# Sheet1.net
KiCad netlist of a schematic drawn in Altium Designer
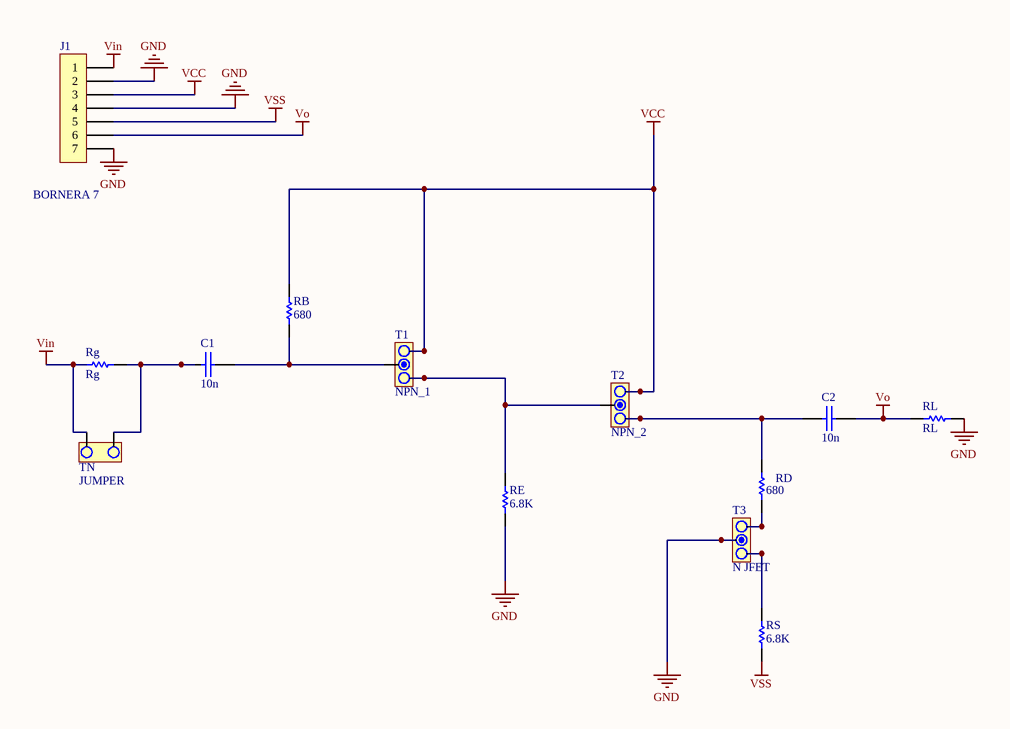
[diagram p0: Sheet1.SchDoc]

(export (version "E")
  (design (tool "Eeschema 10.0.6"))
  (components
    (comp (ref "C1") (value "10n") (footprint "0805") (libsource (lib "LIBEBAL") (part "CAP")))
    (comp (ref "C2") (value "10n") (footprint "0805") (libsource (lib "LIBEBAL") (part "CAP")))
    (comp (ref "J1")
      (value "BORNERA 7")
      (footprint "BORNERA7")
      (libsource (lib "LIBEBAL") (part "BORNERA 7"))
    )
    (comp (ref "RB") (value "680") (footprint "0805") (libsource (lib "LIBEBAL") (part "RES")))
    (comp (ref "RD") (value "680") (footprint "0805") (libsource (lib "LIBEBAL") (part "RES")))
    (comp (ref "RE") (value "6.8K") (footprint "0805") (libsource (lib "LIBEBAL") (part "RES")))
    (comp (ref "Rg") (value "Rg") (footprint "0805") (libsource (lib "LIBEBAL") (part "RES")))
    (comp (ref "RL") (value "RL") (footprint "0805") (libsource (lib "LIBEBAL") (part "RES")))
    (comp (ref "RS") (value "6.8K") (footprint "0805") (libsource (lib "LIBEBAL") (part "RES")))
    (comp (ref "T1") (value "NPN_1") (footprint "JUMPER3") (libsource (lib "LIBEBAL") (part "JUMPER3")))
    (comp (ref "T2") (value "NPN_2") (footprint "JUMPER3") (libsource (lib "LIBEBAL") (part "JUMPER3")))
    (comp (ref "T3") (value "N JFET") (footprint "JUMPER3") (libsource (lib "LIBEBAL") (part "JUMPER3")))
    (comp (ref "TN") (value "JUMPER") (footprint "JUMPER2") (libsource (lib "LIBEBAL") (part "JUMPER")))
  )
  (nets
    (net (code "1") (name "GND") (class "Default")
      (node (ref "J1") (pin "2") (pinfunction "2_2") (pintype "passive"))
      (node (ref "J1") (pin "4") (pinfunction "4_4") (pintype "passive"))
      (node (ref "J1") (pin "7") (pinfunction "7_7") (pintype "passive"))
      (node (ref "RE") (pin "1") (pinfunction "1_1") (pintype "passive"))
      (node (ref "RL") (pin "2") (pinfunction "2_2") (pintype "passive"))
      (node (ref "T3") (pin "2") (pinfunction "2_2") (pintype "passive"))
    )
    (net (code "2") (name "Net-(C1-Pad1)") (class "Default")
      (node (ref "C1") (pin "1") (pinfunction "1_1") (pintype "passive"))
      (node (ref "Rg") (pin "2") (pinfunction "2_2") (pintype "passive"))
      (node (ref "TN") (pin "2") (pinfunction "2_2") (pintype "passive"))
    )
    (net (code "3") (name "Net-(C1-Pad2)") (class "Default")
      (node (ref "C1") (pin "2") (pinfunction "2_2") (pintype "passive"))
      (node (ref "RB") (pin "1") (pinfunction "1_1") (pintype "passive"))
      (node (ref "T1") (pin "2") (pinfunction "2_2") (pintype "passive"))
    )
    (net (code "4") (name "Net-(C2-Pad1)") (class "Default")
      (node (ref "C2") (pin "1") (pinfunction "1_1") (pintype "passive"))
      (node (ref "RD") (pin "2") (pinfunction "2_2") (pintype "passive"))
      (node (ref "T2") (pin "3") (pinfunction "3_3") (pintype "passive"))
    )
    (net (code "5") (name "Net-(RD-Pad1)") (class "Default")
      (node (ref "RD") (pin "1") (pinfunction "1_1") (pintype "passive"))
      (node (ref "T3") (pin "1") (pinfunction "1_1") (pintype "passive"))
    )
    (net (code "6") (name "Net-(RE-Pad2)") (class "Default")
      (node (ref "RE") (pin "2") (pinfunction "2_2") (pintype "passive"))
      (node (ref "T1") (pin "3") (pinfunction "3_3") (pintype "passive"))
      (node (ref "T2") (pin "2") (pinfunction "2_2") (pintype "passive"))
    )
    (net (code "7") (name "Net-(RS-Pad2)") (class "Default")
      (node (ref "RS") (pin "2") (pinfunction "2_2") (pintype "passive"))
      (node (ref "T3") (pin "3") (pinfunction "3_3") (pintype "passive"))
    )
    (net (code "8") (name "VCC") (class "Default")
      (node (ref "J1") (pin "3") (pinfunction "3_3") (pintype "passive"))
      (node (ref "RB") (pin "2") (pinfunction "2_2") (pintype "passive"))
      (node (ref "T1") (pin "1") (pinfunction "1_1") (pintype "passive"))
      (node (ref "T2") (pin "1") (pinfunction "1_1") (pintype "passive"))
    )
    (net (code "9") (name "VSS") (class "Default")
      (node (ref "J1") (pin "5") (pinfunction "5_5") (pintype "passive"))
      (node (ref "RS") (pin "1") (pinfunction "1_1") (pintype "passive"))
    )
    (net (code "10") (name "Vin") (class "Default")
      (node (ref "J1") (pin "1") (pinfunction "1_1") (pintype "passive"))
      (node (ref "Rg") (pin "1") (pinfunction "1_1") (pintype "passive"))
      (node (ref "TN") (pin "1") (pinfunction "1_1") (pintype "passive"))
    )
    (net (code "11") (name "Vo") (class "Default")
      (node (ref "C2") (pin "2") (pinfunction "2_2") (pintype "passive"))
      (node (ref "J1") (pin "6") (pinfunction "6_6") (pintype "passive"))
      (node (ref "RL") (pin "1") (pinfunction "1_1") (pintype "passive"))
    )
  )
)
